# CPLD.net
KiCad netlist of a schematic drawn in Altium Designer
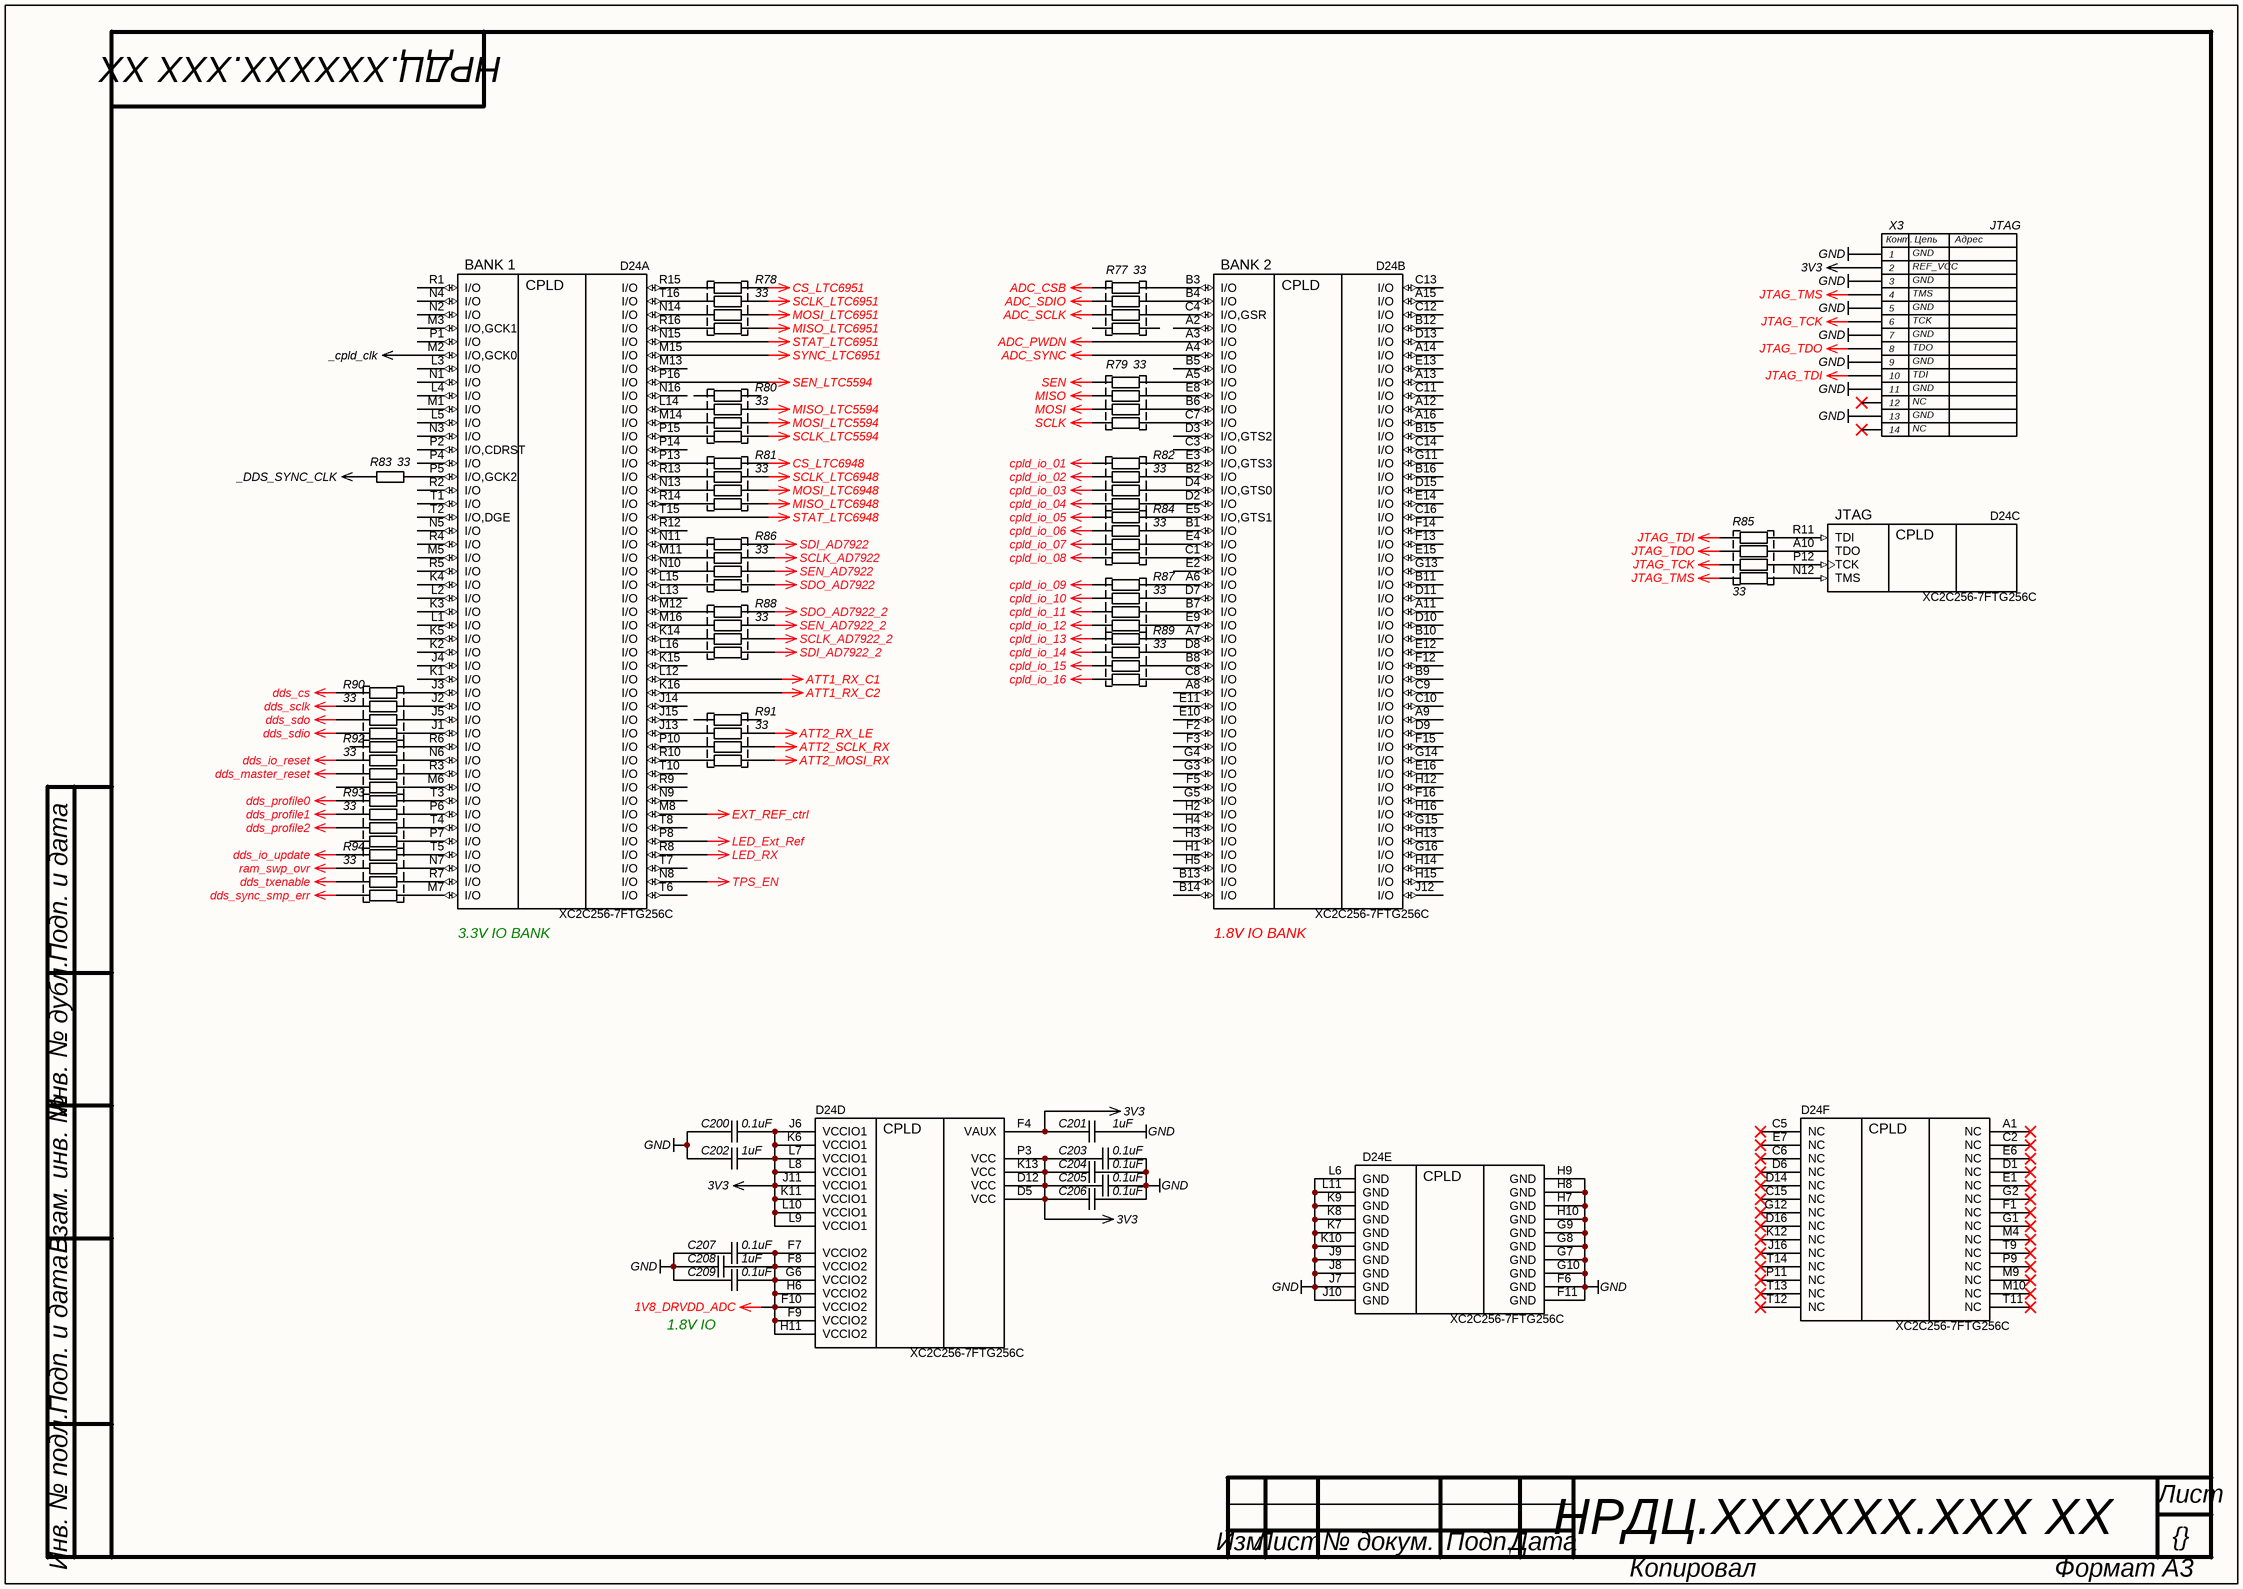
[diagram p0: CPLD.SchDoc]

(export (version "E")
  (design (tool "Eeschema 10.0.6"))
  (components
    (comp (ref "C200")
      (value "0.1uF")
      (footprint "C0402")
      (description "SMD Capacitor")
      (fields (field (name "MANUFACTURER") "Murata") (field (name "TOLERANCE") "10%"))
      (libsource (lib "Kintex_SDR") (part "CAP"))
    )
    (comp (ref "C201")
      (value "1uF")
      (footprint "C0402")
      (description "SMD Capacitor")
      (fields (field (name "MANUFACTURER") "Murata") (field (name "TOLERANCE") "10%"))
      (libsource (lib "Kintex_SDR") (part "CAP"))
    )
    (comp (ref "C202")
      (value "1uF")
      (footprint "C0402")
      (description "SMD Capacitor")
      (fields (field (name "MANUFACTURER") "Murata") (field (name "TOLERANCE") "10%"))
      (libsource (lib "Kintex_SDR") (part "CAP"))
    )
    (comp (ref "C203")
      (value "0.1uF")
      (footprint "C0402")
      (description "SMD Capacitor")
      (fields (field (name "MANUFACTURER") "Murata") (field (name "TOLERANCE") "10%"))
      (libsource (lib "Kintex_SDR") (part "CAP"))
    )
    (comp (ref "C204")
      (value "0.1uF")
      (footprint "C0402")
      (description "SMD Capacitor")
      (fields (field (name "MANUFACTURER") "Murata") (field (name "TOLERANCE") "10%"))
      (libsource (lib "Kintex_SDR") (part "CAP"))
    )
    (comp (ref "C205")
      (value "0.1uF")
      (footprint "C0402")
      (description "SMD Capacitor")
      (fields (field (name "MANUFACTURER") "Murata") (field (name "TOLERANCE") "10%"))
      (libsource (lib "Kintex_SDR") (part "CAP"))
    )
    (comp (ref "C206")
      (value "0.1uF")
      (footprint "C0402")
      (description "SMD Capacitor")
      (fields (field (name "MANUFACTURER") "Murata") (field (name "TOLERANCE") "10%"))
      (libsource (lib "Kintex_SDR") (part "CAP"))
    )
    (comp (ref "C207")
      (value "0.1uF")
      (footprint "C0402")
      (description "SMD Capacitor")
      (fields (field (name "MANUFACTURER") "Murata") (field (name "TOLERANCE") "10%"))
      (libsource (lib "Kintex_SDR") (part "CAP"))
    )
    (comp (ref "C208")
      (value "1uF")
      (footprint "C0402")
      (description "SMD Capacitor")
      (fields (field (name "MANUFACTURER") "Murata") (field (name "TOLERANCE") "10%"))
      (libsource (lib "Kintex_SDR") (part "CAP"))
    )
    (comp (ref "C209")
      (value "0.1uF")
      (footprint "C0402")
      (description "SMD Capacitor")
      (fields (field (name "MANUFACTURER") "Murata") (field (name "TOLERANCE") "10%"))
      (libsource (lib "Kintex_SDR") (part "CAP"))
    )
    (comp (ref "D24")
      (value "XC2C256-7FTG256C")
      (footprint "DBLib:FTG256")
      (description "CoolRunner-II 1.8V, 256 Macrocell CPLD, 184 User I/Os, 256-Ball FTBGA, Commercial Grade, Pb-Free")
      (libsource (lib "DBLib") (part "XC2C256-7FTG256C"))
    )
    (comp (ref "R77")
      (value "33")
      (footprint "EXN8V")
      (description "Chip Resistor Array")
      (fields (field (name "TOLERANCE") "5%") (field (name "MANUFACTURER") "Panasonic"))
      (libsource (lib "Kintex_SDR") (part "RES 4x0402"))
    )
    (comp (ref "R78")
      (value "33")
      (footprint "EXN8V")
      (description "Chip Resistor Array")
      (fields (field (name "TOLERANCE") "5%") (field (name "MANUFACTURER") "Panasonic"))
      (libsource (lib "Kintex_SDR") (part "RES 4x0402"))
    )
    (comp (ref "R79")
      (value "33")
      (footprint "EXN8V")
      (description "Chip Resistor Array")
      (fields (field (name "TOLERANCE") "5%") (field (name "MANUFACTURER") "Panasonic"))
      (libsource (lib "Kintex_SDR") (part "RES 4x0402"))
    )
    (comp (ref "R80")
      (value "33")
      (footprint "EXN8V")
      (description "Chip Resistor Array")
      (fields (field (name "TOLERANCE") "5%") (field (name "MANUFACTURER") "Panasonic"))
      (libsource (lib "Kintex_SDR") (part "RES 4x0402"))
    )
    (comp (ref "R81")
      (value "33")
      (footprint "EXN8V")
      (description "Chip Resistor Array")
      (fields (field (name "TOLERANCE") "5%") (field (name "MANUFACTURER") "Panasonic"))
      (libsource (lib "Kintex_SDR") (part "RES 4x0402"))
    )
    (comp (ref "R82")
      (value "33")
      (footprint "EXN8V")
      (description "Chip Resistor Array")
      (fields (field (name "TOLERANCE") "5%") (field (name "MANUFACTURER") "Panasonic"))
      (libsource (lib "Kintex_SDR") (part "RES 4x0402"))
    )
    (comp (ref "R83")
      (value "33")
      (footprint "R0402")
      (description "SMD Resistor")
      (fields (field (name "POWER") "0.062 Wt") (field (name "TOLERANCE") "5%"))
      (libsource (lib "Kintex_SDR") (part "RES"))
    )
    (comp (ref "R84")
      (value "33")
      (footprint "EXN8V")
      (description "Chip Resistor Array")
      (fields (field (name "TOLERANCE") "5%") (field (name "MANUFACTURER") "Panasonic"))
      (libsource (lib "Kintex_SDR") (part "RES 4x0402"))
    )
    (comp (ref "R85")
      (value "33")
      (footprint "EXN8V")
      (description "Chip Resistor Array")
      (fields (field (name "TOLERANCE") "5%") (field (name "MANUFACTURER") "Panasonic"))
      (libsource (lib "") (part "RES 4x0402_1"))
    )
    (comp (ref "R86")
      (value "33")
      (footprint "EXN8V")
      (description "Chip Resistor Array")
      (fields (field (name "TOLERANCE") "5%") (field (name "MANUFACTURER") "Panasonic"))
      (libsource (lib "Kintex_SDR") (part "RES 4x0402"))
    )
    (comp (ref "R87")
      (value "33")
      (footprint "EXN8V")
      (description "Chip Resistor Array")
      (fields (field (name "TOLERANCE") "5%") (field (name "MANUFACTURER") "Panasonic"))
      (libsource (lib "Kintex_SDR") (part "RES 4x0402"))
    )
    (comp (ref "R88")
      (value "33")
      (footprint "EXN8V")
      (description "Chip Resistor Array")
      (fields (field (name "TOLERANCE") "5%") (field (name "MANUFACTURER") "Panasonic"))
      (libsource (lib "Kintex_SDR") (part "RES 4x0402"))
    )
    (comp (ref "R89")
      (value "33")
      (footprint "EXN8V")
      (description "Chip Resistor Array")
      (fields (field (name "TOLERANCE") "5%") (field (name "MANUFACTURER") "Panasonic"))
      (libsource (lib "Kintex_SDR") (part "RES 4x0402"))
    )
    (comp (ref "R90")
      (value "33")
      (footprint "EXN8V")
      (description "Chip Resistor Array")
      (fields (field (name "TOLERANCE") "5%") (field (name "MANUFACTURER") "Panasonic"))
      (libsource (lib "Kintex_SDR") (part "RES 4x0402"))
    )
    (comp (ref "R91")
      (value "33")
      (footprint "EXN8V")
      (description "Chip Resistor Array")
      (fields (field (name "TOLERANCE") "5%") (field (name "MANUFACTURER") "Panasonic"))
      (libsource (lib "Kintex_SDR") (part "RES 4x0402"))
    )
    (comp (ref "R92")
      (value "33")
      (footprint "EXN8V")
      (description "Chip Resistor Array")
      (fields (field (name "TOLERANCE") "5%") (field (name "MANUFACTURER") "Panasonic"))
      (libsource (lib "Kintex_SDR") (part "RES 4x0402"))
    )
    (comp (ref "R93")
      (value "33")
      (footprint "EXN8V")
      (description "Chip Resistor Array")
      (fields (field (name "TOLERANCE") "5%") (field (name "MANUFACTURER") "Panasonic"))
      (libsource (lib "Kintex_SDR") (part "RES 4x0402"))
    )
    (comp (ref "R94")
      (value "33")
      (footprint "EXN8V")
      (description "Chip Resistor Array")
      (fields (field (name "TOLERANCE") "5%") (field (name "MANUFACTURER") "Panasonic"))
      (libsource (lib "Kintex_SDR") (part "RES 4x0402"))
    )
    (comp (ref "X3")
      (value "JTAG")
      (footprint "DBLib:JTAG Mail 2mm")
      (description "2.00mm Pitch, Milli-Grid PCB Header, Dual Row, Vertical, Through Hole, Shrouded, 14\r\nCircuits")
      (fields (field (name "MANUFACTURER") "Molex"))
      (libsource (lib "DBLib") (part "HDR Debug_14-pin"))
    )
  )
  (nets
    (net (code "1") (name "1V8_DRVDD_ADC") (class "Default")
      (node (ref "C207") (pin "2") (pinfunction "2_2") (pintype "passive"))
      (node (ref "C208") (pin "2") (pinfunction "2_2") (pintype "passive"))
      (node (ref "C209") (pin "2") (pinfunction "2_2") (pintype "passive"))
      (node (ref "D24") (pin "F10") (pinfunction "VCCIO2_F10") (pintype "power_in"))
      (node (ref "D24") (pin "F7") (pinfunction "VCCIO2_F7") (pintype "power_in"))
      (node (ref "D24") (pin "F8") (pinfunction "VCCIO2_F8") (pintype "power_in"))
      (node (ref "D24") (pin "F9") (pinfunction "VCCIO2_F9") (pintype "power_in"))
      (node (ref "D24") (pin "G6") (pinfunction "VCCIO2_G6") (pintype "power_in"))
      (node (ref "D24") (pin "H11") (pinfunction "VCCIO2_H11") (pintype "power_in"))
      (node (ref "D24") (pin "H6") (pinfunction "VCCIO2_H6") (pintype "power_in"))
    )
    (net (code "2") (name "3V3") (class "Default")
      (node (ref "C200") (pin "2") (pinfunction "2_2") (pintype "passive"))
      (node (ref "C201") (pin "1") (pinfunction "1_1") (pintype "passive"))
      (node (ref "C202") (pin "2") (pinfunction "2_2") (pintype "passive"))
      (node (ref "C203") (pin "1") (pinfunction "1_1") (pintype "passive"))
      (node (ref "C204") (pin "1") (pinfunction "1_1") (pintype "passive"))
      (node (ref "C205") (pin "1") (pinfunction "1_1") (pintype "passive"))
      (node (ref "C206") (pin "1") (pinfunction "1_1") (pintype "passive"))
      (node (ref "D24") (pin "D12") (pinfunction "VCC_D12") (pintype "power_in"))
      (node (ref "D24") (pin "D5") (pinfunction "VCC_D5") (pintype "power_in"))
      (node (ref "D24") (pin "F4") (pinfunction "VAUX_F4") (pintype "power_in"))
      (node (ref "D24") (pin "J11") (pinfunction "VCCIO1_J11") (pintype "power_in"))
      (node (ref "D24") (pin "J6") (pinfunction "VCCIO1_J6") (pintype "power_in"))
      (node (ref "D24") (pin "K11") (pinfunction "VCCIO1_K11") (pintype "power_in"))
      (node (ref "D24") (pin "K13") (pinfunction "VCC_K13") (pintype "power_in"))
      (node (ref "D24") (pin "K6") (pinfunction "VCCIO1_K6") (pintype "power_in"))
      (node (ref "D24") (pin "L10") (pinfunction "VCCIO1_L10") (pintype "power_in"))
      (node (ref "D24") (pin "L7") (pinfunction "VCCIO1_L7") (pintype "power_in"))
      (node (ref "D24") (pin "L8") (pinfunction "VCCIO1_L8") (pintype "power_in"))
      (node (ref "D24") (pin "L9") (pinfunction "VCCIO1_L9") (pintype "power_in"))
      (node (ref "D24") (pin "P3") (pinfunction "VCC_P3") (pintype "power_in"))
      (node (ref "X3") (pin "2") (pinfunction "2_2") (pintype "passive"))
    )
    (net (code "3") (name "ADC_CSB") (class "Default")
      (node (ref "R77") (pin "5") (pinfunction "5_5") (pintype "passive"))
    )
    (net (code "4") (name "ADC_PWDN") (class "Default")
      (node (ref "D24") (pin "A3") (pinfunction "I/O_A3") (pintype "bidirectional"))
    )
    (net (code "5") (name "ADC_SCLK") (class "Default")
      (node (ref "R77") (pin "7") (pinfunction "7_7") (pintype "passive"))
    )
    (net (code "6") (name "ADC_SDIO") (class "Default")
      (node (ref "R77") (pin "6") (pinfunction "6_6") (pintype "passive"))
    )
    (net (code "7") (name "ADC_SYNC") (class "Default")
      (node (ref "D24") (pin "A4") (pinfunction "I/O_A4") (pintype "bidirectional"))
    )
    (net (code "8") (name "ATT1_RX_C1") (class "Default")
      (node (ref "D24") (pin "L12") (pinfunction "I/O_L12") (pintype "bidirectional"))
    )
    (net (code "9") (name "ATT1_RX_C2") (class "Default")
      (node (ref "D24") (pin "K16") (pinfunction "I/O_K16") (pintype "bidirectional"))
    )
    (net (code "10") (name "ATT2_MOSI_RX") (class "Default")
      (node (ref "R91") (pin "1") (pinfunction "1_1") (pintype "passive"))
    )
    (net (code "11") (name "ATT2_RX_LE") (class "Default")
      (node (ref "R91") (pin "3") (pinfunction "3_3") (pintype "passive"))
    )
    (net (code "12") (name "ATT2_SCLK_RX") (class "Default")
      (node (ref "R91") (pin "2") (pinfunction "2_2") (pintype "passive"))
    )
    (net (code "13") (name "CS_LTC6948") (class "Default")
      (node (ref "R81") (pin "4") (pinfunction "4_4") (pintype "passive"))
    )
    (net (code "14") (name "CS_LTC6951") (class "Default")
      (node (ref "R78") (pin "4") (pinfunction "4_4") (pintype "passive"))
    )
    (net (code "15") (name "EXT_REF_ctrl") (class "Default")
      (node (ref "D24") (pin "M8") (pinfunction "I/O_M8") (pintype "bidirectional"))
    )
    (net (code "16") (name "GND") (class "Default")
      (node (ref "C200") (pin "1") (pinfunction "1_1") (pintype "passive"))
      (node (ref "C201") (pin "2") (pinfunction "2_2") (pintype "passive"))
      (node (ref "C202") (pin "1") (pinfunction "1_1") (pintype "passive"))
      (node (ref "C203") (pin "2") (pinfunction "2_2") (pintype "passive"))
      (node (ref "C204") (pin "2") (pinfunction "2_2") (pintype "passive"))
      (node (ref "C205") (pin "2") (pinfunction "2_2") (pintype "passive"))
      (node (ref "C206") (pin "2") (pinfunction "2_2") (pintype "passive"))
      (node (ref "C207") (pin "1") (pinfunction "1_1") (pintype "passive"))
      (node (ref "C208") (pin "1") (pinfunction "1_1") (pintype "passive"))
      (node (ref "C209") (pin "1") (pinfunction "1_1") (pintype "passive"))
      (node (ref "D24") (pin "F11") (pinfunction "GND_F11") (pintype "power_in"))
      (node (ref "D24") (pin "F6") (pinfunction "GND_F6") (pintype "power_in"))
      (node (ref "D24") (pin "G10") (pinfunction "GND_G10") (pintype "power_in"))
      (node (ref "D24") (pin "G7") (pinfunction "GND_G7") (pintype "power_in"))
      (node (ref "D24") (pin "G8") (pinfunction "GND_G8") (pintype "power_in"))
      (node (ref "D24") (pin "G9") (pinfunction "GND_G9") (pintype "power_in"))
      (node (ref "D24") (pin "H10") (pinfunction "GND_H10") (pintype "power_in"))
      (node (ref "D24") (pin "H7") (pinfunction "GND_H7") (pintype "power_in"))
      (node (ref "D24") (pin "H8") (pinfunction "GND_H8") (pintype "power_in"))
      (node (ref "D24") (pin "H9") (pinfunction "GND_H9") (pintype "power_in"))
      (node (ref "D24") (pin "J10") (pinfunction "GND_J10") (pintype "power_in"))
      (node (ref "D24") (pin "J7") (pinfunction "GND_J7") (pintype "power_in"))
      (node (ref "D24") (pin "J8") (pinfunction "GND_J8") (pintype "power_in"))
      (node (ref "D24") (pin "J9") (pinfunction "GND_J9") (pintype "power_in"))
      (node (ref "D24") (pin "K10") (pinfunction "GND_K10") (pintype "power_in"))
      (node (ref "D24") (pin "K7") (pinfunction "GND_K7") (pintype "power_in"))
      (node (ref "D24") (pin "K8") (pinfunction "GND_K8") (pintype "power_in"))
      (node (ref "D24") (pin "K9") (pinfunction "GND_K9") (pintype "power_in"))
      (node (ref "D24") (pin "L11") (pinfunction "GND_L11") (pintype "power_in"))
      (node (ref "D24") (pin "L6") (pinfunction "GND_L6") (pintype "power_in"))
      (node (ref "X3") (pin "1") (pinfunction "1_1") (pintype "passive"))
      (node (ref "X3") (pin "11") (pinfunction "11_11") (pintype "passive"))
      (node (ref "X3") (pin "13") (pinfunction "13_13") (pintype "passive"))
      (node (ref "X3") (pin "3") (pinfunction "3_3") (pintype "passive"))
      (node (ref "X3") (pin "5") (pinfunction "5_5") (pintype "passive"))
      (node (ref "X3") (pin "7") (pinfunction "7_7") (pintype "passive"))
      (node (ref "X3") (pin "9") (pinfunction "9_9") (pintype "passive"))
    )
    (net (code "17") (name "JTAG_TCK") (class "Default")
      (node (ref "R85") (pin "6") (pinfunction "6_6") (pintype "passive"))
      (node (ref "X3") (pin "6") (pinfunction "6_6") (pintype "passive"))
    )
    (net (code "18") (name "JTAG_TDI") (class "Default")
      (node (ref "R85") (pin "8") (pinfunction "8_8") (pintype "passive"))
      (node (ref "X3") (pin "10") (pinfunction "10_10") (pintype "passive"))
    )
    (net (code "19") (name "JTAG_TDO") (class "Default")
      (node (ref "R85") (pin "7") (pinfunction "7_7") (pintype "passive"))
      (node (ref "X3") (pin "8") (pinfunction "8_8") (pintype "passive"))
    )
    (net (code "20") (name "JTAG_TMS") (class "Default")
      (node (ref "R85") (pin "5") (pinfunction "5_5") (pintype "passive"))
      (node (ref "X3") (pin "4") (pinfunction "4_4") (pintype "passive"))
    )
    (net (code "21") (name "LED_Ext_Ref") (class "Default")
      (node (ref "D24") (pin "P8") (pinfunction "I/O_P8") (pintype "bidirectional"))
    )
    (net (code "22") (name "LED_RX") (class "Default")
      (node (ref "D24") (pin "R8") (pinfunction "I/O_R8") (pintype "bidirectional"))
    )
    (net (code "23") (name "MISO") (class "Default")
      (node (ref "R79") (pin "6") (pinfunction "6_6") (pintype "passive"))
    )
    (net (code "24") (name "MISO_LTC5594") (class "Default")
      (node (ref "R80") (pin "3") (pinfunction "3_3") (pintype "passive"))
    )
    (net (code "25") (name "MISO_LTC6948") (class "Default")
      (node (ref "R81") (pin "1") (pinfunction "1_1") (pintype "passive"))
    )
    (net (code "26") (name "MISO_LTC6951") (class "Default")
      (node (ref "R78") (pin "1") (pinfunction "1_1") (pintype "passive"))
    )
    (net (code "27") (name "MOSI") (class "Default")
      (node (ref "R79") (pin "7") (pinfunction "7_7") (pintype "passive"))
    )
    (net (code "28") (name "MOSI_LTC5594") (class "Default")
      (node (ref "R80") (pin "2") (pinfunction "2_2") (pintype "passive"))
    )
    (net (code "29") (name "MOSI_LTC6948") (class "Default")
      (node (ref "R81") (pin "2") (pinfunction "2_2") (pintype "passive"))
    )
    (net (code "30") (name "MOSI_LTC6951") (class "Default")
      (node (ref "R78") (pin "2") (pinfunction "2_2") (pintype "passive"))
    )
    (net (code "31") (name "Net-(D24A-I{slash}O,GCK2)") (class "Default")
      (node (ref "D24") (pin "P5") (pinfunction "I/O,GCK2_P5") (pintype "bidirectional"))
      (node (ref "R83") (pin "2") (pinfunction "2_2") (pintype "passive"))
    )
    (net (code "32") (name "Net-(D24A-I{slash}O-PadJ1)") (class "Default")
      (node (ref "D24") (pin "J1") (pinfunction "I/O_J1") (pintype "bidirectional"))
      (node (ref "R90") (pin "1") (pinfunction "1_1") (pintype "passive"))
    )
    (net (code "33") (name "Net-(D24A-I{slash}O-PadJ2)") (class "Default")
      (node (ref "D24") (pin "J2") (pinfunction "I/O_J2") (pintype "bidirectional"))
      (node (ref "R90") (pin "3") (pinfunction "3_3") (pintype "passive"))
    )
    (net (code "34") (name "Net-(D24A-I{slash}O-PadJ3)") (class "Default")
      (node (ref "D24") (pin "J3") (pinfunction "I/O_J3") (pintype "bidirectional"))
      (node (ref "R90") (pin "4") (pinfunction "4_4") (pintype "passive"))
    )
    (net (code "35") (name "Net-(D24A-I{slash}O-PadJ5)") (class "Default")
      (node (ref "D24") (pin "J5") (pinfunction "I/O_J5") (pintype "bidirectional"))
      (node (ref "R90") (pin "2") (pinfunction "2_2") (pintype "passive"))
    )
    (net (code "36") (name "Net-(D24A-I{slash}O-PadJ13)") (class "Default")
      (node (ref "D24") (pin "J13") (pinfunction "I/O_J13") (pintype "bidirectional"))
      (node (ref "R91") (pin "6") (pinfunction "6_6") (pintype "passive"))
    )
    (net (code "37") (name "Net-(D24A-I{slash}O-PadK14)") (class "Default")
      (node (ref "D24") (pin "K14") (pinfunction "I/O_K14") (pintype "bidirectional"))
      (node (ref "R88") (pin "7") (pinfunction "7_7") (pintype "passive"))
    )
    (net (code "38") (name "Net-(D24A-I{slash}O-PadL14)") (class "Default")
      (node (ref "D24") (pin "L14") (pinfunction "I/O_L14") (pintype "bidirectional"))
      (node (ref "R80") (pin "6") (pinfunction "6_6") (pintype "passive"))
    )
    (net (code "39") (name "Net-(D24A-I{slash}O-PadL15)") (class "Default")
      (node (ref "D24") (pin "L15") (pinfunction "I/O_L15") (pintype "bidirectional"))
      (node (ref "R86") (pin "8") (pinfunction "8_8") (pintype "passive"))
    )
    (net (code "40") (name "Net-(D24A-I{slash}O-PadL16)") (class "Default")
      (node (ref "D24") (pin "L16") (pinfunction "I/O_L16") (pintype "bidirectional"))
      (node (ref "R88") (pin "8") (pinfunction "8_8") (pintype "passive"))
    )
    (net (code "41") (name "Net-(D24A-I{slash}O-PadM6)") (class "Default")
      (node (ref "D24") (pin "M6") (pinfunction "I/O_M6") (pintype "bidirectional"))
      (node (ref "R92") (pin "1") (pinfunction "1_1") (pintype "passive"))
    )
    (net (code "42") (name "Net-(D24A-I{slash}O-PadM7)") (class "Default")
      (node (ref "D24") (pin "M7") (pinfunction "I/O_M7") (pintype "bidirectional"))
      (node (ref "R94") (pin "1") (pinfunction "1_1") (pintype "passive"))
    )
    (net (code "43") (name "Net-(D24A-I{slash}O-PadM11)") (class "Default")
      (node (ref "D24") (pin "M11") (pinfunction "I/O_M11") (pintype "bidirectional"))
      (node (ref "R86") (pin "6") (pinfunction "6_6") (pintype "passive"))
    )
    (net (code "44") (name "Net-(D24A-I{slash}O-PadM12)") (class "Default")
      (node (ref "D24") (pin "M12") (pinfunction "I/O_M12") (pintype "bidirectional"))
      (node (ref "R88") (pin "5") (pinfunction "5_5") (pintype "passive"))
    )
    (net (code "45") (name "Net-(D24A-I{slash}O-PadM14)") (class "Default")
      (node (ref "D24") (pin "M14") (pinfunction "I/O_M14") (pintype "bidirectional"))
      (node (ref "R80") (pin "7") (pinfunction "7_7") (pintype "passive"))
    )
    (net (code "46") (name "Net-(D24A-I{slash}O-PadM16)") (class "Default")
      (node (ref "D24") (pin "M16") (pinfunction "I/O_M16") (pintype "bidirectional"))
      (node (ref "R88") (pin "6") (pinfunction "6_6") (pintype "passive"))
    )
    (net (code "47") (name "Net-(D24A-I{slash}O-PadN6)") (class "Default")
      (node (ref "D24") (pin "N6") (pinfunction "I/O_N6") (pintype "bidirectional"))
      (node (ref "R92") (pin "3") (pinfunction "3_3") (pintype "passive"))
    )
    (net (code "48") (name "Net-(D24A-I{slash}O-PadN7)") (class "Default")
      (node (ref "D24") (pin "N7") (pinfunction "I/O_N7") (pintype "bidirectional"))
      (node (ref "R94") (pin "3") (pinfunction "3_3") (pintype "passive"))
    )
    (net (code "49") (name "Net-(D24A-I{slash}O-PadN10)") (class "Default")
      (node (ref "D24") (pin "N10") (pinfunction "I/O_N10") (pintype "bidirectional"))
      (node (ref "R86") (pin "7") (pinfunction "7_7") (pintype "passive"))
    )
    (net (code "50") (name "Net-(D24A-I{slash}O-PadN11)") (class "Default")
      (node (ref "D24") (pin "N11") (pinfunction "I/O_N11") (pintype "bidirectional"))
      (node (ref "R86") (pin "5") (pinfunction "5_5") (pintype "passive"))
    )
    (net (code "51") (name "Net-(D24A-I{slash}O-PadN13)") (class "Default")
      (node (ref "D24") (pin "N13") (pinfunction "I/O_N13") (pintype "bidirectional"))
      (node (ref "R81") (pin "7") (pinfunction "7_7") (pintype "passive"))
    )
    (net (code "52") (name "Net-(D24A-I{slash}O-PadN14)") (class "Default")
      (node (ref "D24") (pin "N14") (pinfunction "I/O_N14") (pintype "bidirectional"))
      (node (ref "R78") (pin "7") (pinfunction "7_7") (pintype "passive"))
    )
    (net (code "53") (name "Net-(D24A-I{slash}O-PadP6)") (class "Default")
      (node (ref "D24") (pin "P6") (pinfunction "I/O_P6") (pintype "bidirectional"))
      (node (ref "R93") (pin "3") (pinfunction "3_3") (pintype "passive"))
    )
    (net (code "54") (name "Net-(D24A-I{slash}O-PadP7)") (class "Default")
      (node (ref "D24") (pin "P7") (pinfunction "I/O_P7") (pintype "bidirectional"))
      (node (ref "R93") (pin "1") (pinfunction "1_1") (pintype "passive"))
    )
    (net (code "55") (name "Net-(D24A-I{slash}O-PadP10)") (class "Default")
      (node (ref "D24") (pin "P10") (pinfunction "I/O_P10") (pintype "bidirectional"))
      (node (ref "R91") (pin "7") (pinfunction "7_7") (pintype "passive"))
    )
    (net (code "56") (name "Net-(D24A-I{slash}O-PadP13)") (class "Default")
      (node (ref "D24") (pin "P13") (pinfunction "I/O_P13") (pintype "bidirectional"))
      (node (ref "R81") (pin "5") (pinfunction "5_5") (pintype "passive"))
    )
    (net (code "57") (name "Net-(D24A-I{slash}O-PadP15)") (class "Default")
      (node (ref "D24") (pin "P15") (pinfunction "I/O_P15") (pintype "bidirectional"))
      (node (ref "R80") (pin "8") (pinfunction "8_8") (pintype "passive"))
    )
    (net (code "58") (name "Net-(D24A-I{slash}O-PadR3)") (class "Default")
      (node (ref "D24") (pin "R3") (pinfunction "I/O_R3") (pintype "bidirectional"))
      (node (ref "R92") (pin "2") (pinfunction "2_2") (pintype "passive"))
    )
    (net (code "59") (name "Net-(D24A-I{slash}O-PadR6)") (class "Default")
      (node (ref "D24") (pin "R6") (pinfunction "I/O_R6") (pintype "bidirectional"))
      (node (ref "R92") (pin "4") (pinfunction "4_4") (pintype "passive"))
    )
    (net (code "60") (name "Net-(D24A-I{slash}O-PadR7)") (class "Default")
      (node (ref "D24") (pin "R7") (pinfunction "I/O_R7") (pintype "bidirectional"))
      (node (ref "R94") (pin "2") (pinfunction "2_2") (pintype "passive"))
    )
    (net (code "61") (name "Net-(D24A-I{slash}O-PadR10)") (class "Default")
      (node (ref "D24") (pin "R10") (pinfunction "I/O_R10") (pintype "bidirectional"))
      (node (ref "R91") (pin "8") (pinfunction "8_8") (pintype "passive"))
    )
    (net (code "62") (name "Net-(D24A-I{slash}O-PadR13)") (class "Default")
      (node (ref "D24") (pin "R13") (pinfunction "I/O_R13") (pintype "bidirectional"))
      (node (ref "R81") (pin "6") (pinfunction "6_6") (pintype "passive"))
    )
    (net (code "63") (name "Net-(D24A-I{slash}O-PadR14)") (class "Default")
      (node (ref "D24") (pin "R14") (pinfunction "I/O_R14") (pintype "bidirectional"))
      (node (ref "R81") (pin "8") (pinfunction "8_8") (pintype "passive"))
    )
    (net (code "64") (name "Net-(D24A-I{slash}O-PadR15)") (class "Default")
      (node (ref "D24") (pin "R15") (pinfunction "I/O_R15") (pintype "bidirectional"))
      (node (ref "R78") (pin "5") (pinfunction "5_5") (pintype "passive"))
    )
    (net (code "65") (name "Net-(D24A-I{slash}O-PadR16)") (class "Default")
      (node (ref "D24") (pin "R16") (pinfunction "I/O_R16") (pintype "bidirectional"))
      (node (ref "R78") (pin "8") (pinfunction "8_8") (pintype "passive"))
    )
    (net (code "66") (name "Net-(D24A-I{slash}O-PadT3)") (class "Default")
      (node (ref "D24") (pin "T3") (pinfunction "I/O_T3") (pintype "bidirectional"))
      (node (ref "R93") (pin "4") (pinfunction "4_4") (pintype "passive"))
    )
    (net (code "67") (name "Net-(D24A-I{slash}O-PadT4)") (class "Default")
      (node (ref "D24") (pin "T4") (pinfunction "I/O_T4") (pintype "bidirectional"))
      (node (ref "R93") (pin "2") (pinfunction "2_2") (pintype "passive"))
    )
    (net (code "68") (name "Net-(D24A-I{slash}O-PadT5)") (class "Default")
      (node (ref "D24") (pin "T5") (pinfunction "I/O_T5") (pintype "bidirectional"))
      (node (ref "R94") (pin "4") (pinfunction "4_4") (pintype "passive"))
    )
    (net (code "69") (name "Net-(D24A-I{slash}O-PadT16)") (class "Default")
      (node (ref "D24") (pin "T16") (pinfunction "I/O_T16") (pintype "bidirectional"))
      (node (ref "R78") (pin "6") (pinfunction "6_6") (pintype "passive"))
    )
    (net (code "70") (name "Net-(D24B-I{slash}O,GSR)") (class "Default")
      (node (ref "D24") (pin "C4") (pinfunction "I/O,GSR_C4") (pintype "bidirectional"))
      (node (ref "R77") (pin "2") (pinfunction "2_2") (pintype "passive"))
    )
    (net (code "71") (name "Net-(D24B-I{slash}O,GTS0)") (class "Default")
      (node (ref "D24") (pin "D4") (pinfunction "I/O,GTS0_D4") (pintype "bidirectional"))
      (node (ref "R82") (pin "2") (pinfunction "2_2") (pintype "passive"))
    )
    (net (code "72") (name "Net-(D24B-I{slash}O,GTS1)") (class "Default")
      (node (ref "D24") (pin "E5") (pinfunction "I/O,GTS1_E5") (pintype "bidirectional"))
      (node (ref "R84") (pin "4") (pinfunction "4_4") (pintype "passive"))
    )
    (net (code "73") (name "Net-(D24B-I{slash}O,GTS3)") (class "Default")
      (node (ref "D24") (pin "E3") (pinfunction "I/O,GTS3_E3") (pintype "bidirectional"))
      (node (ref "R82") (pin "4") (pinfunction "4_4") (pintype "passive"))
    )
    (net (code "74") (name "Net-(D24B-I{slash}O-PadA5)") (class "Default")
      (node (ref "D24") (pin "A5") (pinfunction "I/O_A5") (pintype "bidirectional"))
      (node (ref "R79") (pin "4") (pinfunction "4_4") (pintype "passive"))
    )
    (net (code "75") (name "Net-(D24B-I{slash}O-PadA6)") (class "Default")
      (node (ref "D24") (pin "A6") (pinfunction "I/O_A6") (pintype "bidirectional"))
      (node (ref "R87") (pin "4") (pinfunction "4_4") (pintype "passive"))
    )
    (net (code "76") (name "Net-(D24B-I{slash}O-PadA7)") (class "Default")
      (node (ref "D24") (pin "A7") (pinfunction "I/O_A7") (pintype "bidirectional"))
      (node (ref "R89") (pin "4") (pinfunction "4_4") (pintype "passive"))
    )
    (net (code "77") (name "Net-(D24B-I{slash}O-PadB1)") (class "Default")
      (node (ref "D24") (pin "B1") (pinfunction "I/O_B1") (pintype "bidirectional"))
      (node (ref "R84") (pin "3") (pinfunction "3_3") (pintype "passive"))
    )
    (net (code "78") (name "Net-(D24B-I{slash}O-PadB2)") (class "Default")
      (node (ref "D24") (pin "B2") (pinfunction "I/O_B2") (pintype "bidirectional"))
      (node (ref "R82") (pin "3") (pinfunction "3_3") (pintype "passive"))
    )
    (net (code "79") (name "Net-(D24B-I{slash}O-PadB3)") (class "Default")
      (node (ref "D24") (pin "B3") (pinfunction "I/O_B3") (pintype "bidirectional"))
      (node (ref "R77") (pin "4") (pinfunction "4_4") (pintype "passive"))
    )
    (net (code "80") (name "Net-(D24B-I{slash}O-PadB4)") (class "Default")
      (node (ref "D24") (pin "B4") (pinfunction "I/O_B4") (pintype "bidirectional"))
      (node (ref "R77") (pin "3") (pinfunction "3_3") (pintype "passive"))
    )
    (net (code "81") (name "Net-(D24B-I{slash}O-PadB6)") (class "Default")
      (node (ref "D24") (pin "B6") (pinfunction "I/O_B6") (pintype "bidirectional"))
      (node (ref "R79") (pin "2") (pinfunction "2_2") (pintype "passive"))
    )
    (net (code "82") (name "Net-(D24B-I{slash}O-PadB7)") (class "Default")
      (node (ref "D24") (pin "B7") (pinfunction "I/O_B7") (pintype "bidirectional"))
      (node (ref "R87") (pin "2") (pinfunction "2_2") (pintype "passive"))
    )
    (net (code "83") (name "Net-(D24B-I{slash}O-PadB8)") (class "Default")
      (node (ref "D24") (pin "B8") (pinfunction "I/O_B8") (pintype "bidirectional"))
      (node (ref "R89") (pin "2") (pinfunction "2_2") (pintype "passive"))
    )
    (net (code "84") (name "Net-(D24B-I{slash}O-PadC1)") (class "Default")
      (node (ref "D24") (pin "C1") (pinfunction "I/O_C1") (pintype "bidirectional"))
      (node (ref "R84") (pin "1") (pinfunction "1_1") (pintype "passive"))
    )
    (net (code "85") (name "Net-(D24B-I{slash}O-PadC7)") (class "Default")
      (node (ref "D24") (pin "C7") (pinfunction "I/O_C7") (pintype "bidirectional"))
      (node (ref "R79") (pin "1") (pinfunction "1_1") (pintype "passive"))
    )
    (net (code "86") (name "Net-(D24B-I{slash}O-PadC8)") (class "Default")
      (node (ref "D24") (pin "C8") (pinfunction "I/O_C8") (pintype "bidirectional"))
      (node (ref "R89") (pin "1") (pinfunction "1_1") (pintype "passive"))
    )
    (net (code "87") (name "Net-(D24B-I{slash}O-PadD2)") (class "Default")
      (node (ref "D24") (pin "D2") (pinfunction "I/O_D2") (pintype "bidirectional"))
      (node (ref "R82") (pin "1") (pinfunction "1_1") (pintype "passive"))
    )
    (net (code "88") (name "Net-(D24B-I{slash}O-PadD7)") (class "Default")
      (node (ref "D24") (pin "D7") (pinfunction "I/O_D7") (pintype "bidirectional"))
      (node (ref "R87") (pin "3") (pinfunction "3_3") (pintype "passive"))
    )
    (net (code "89") (name "Net-(D24B-I{slash}O-PadD8)") (class "Default")
      (node (ref "D24") (pin "D8") (pinfunction "I/O_D8") (pintype "bidirectional"))
      (node (ref "R89") (pin "3") (pinfunction "3_3") (pintype "passive"))
    )
    (net (code "90") (name "Net-(D24B-I{slash}O-PadE4)") (class "Default")
      (node (ref "D24") (pin "E4") (pinfunction "I/O_E4") (pintype "bidirectional"))
      (node (ref "R84") (pin "2") (pinfunction "2_2") (pintype "passive"))
    )
    (net (code "91") (name "Net-(D24B-I{slash}O-PadE8)") (class "Default")
      (node (ref "D24") (pin "E8") (pinfunction "I/O_E8") (pintype "bidirectional"))
      (node (ref "R79") (pin "3") (pinfunction "3_3") (pintype "passive"))
    )
    (net (code "92") (name "Net-(D24B-I{slash}O-PadE9)") (class "Default")
      (node (ref "D24") (pin "E9") (pinfunction "I/O_E9") (pintype "bidirectional"))
      (node (ref "R87") (pin "1") (pinfunction "1_1") (pintype "passive"))
    )
    (net (code "93") (name "Net-(D24C-TCK)") (class "Default")
      (node (ref "D24") (pin "P12") (pinfunction "TCK_P12") (pintype "input"))
      (node (ref "R85") (pin "3") (pinfunction "3_3") (pintype "passive"))
    )
    (net (code "94") (name "Net-(D24C-TDI)") (class "Default")
      (node (ref "D24") (pin "R11") (pinfunction "TDI_R11") (pintype "input"))
      (node (ref "R85") (pin "1") (pinfunction "1_1") (pintype "passive"))
    )
    (net (code "95") (name "Net-(D24C-TDO)") (class "Default")
      (node (ref "D24") (pin "A10") (pinfunction "TDO_A10") (pintype "passive"))
      (node (ref "R85") (pin "2") (pinfunction "2_2") (pintype "passive"))
    )
    (net (code "96") (name "Net-(D24C-TMS)") (class "Default")
      (node (ref "D24") (pin "N12") (pinfunction "TMS_N12") (pintype "input"))
      (node (ref "R85") (pin "4") (pinfunction "4_4") (pintype "passive"))
    )
    (net (code "97") (name "SCLK") (class "Default")
      (node (ref "R79") (pin "8") (pinfunction "8_8") (pintype "passive"))
    )
    (net (code "98") (name "SCLK_AD7922") (class "Default")
      (node (ref "R86") (pin "3") (pinfunction "3_3") (pintype "passive"))
    )
    (net (code "99") (name "SCLK_AD7922_2") (class "Default")
      (node (ref "R88") (pin "2") (pinfunction "2_2") (pintype "passive"))
    )
    (net (code "100") (name "SCLK_LTC5594") (class "Default")
      (node (ref "R80") (pin "1") (pinfunction "1_1") (pintype "passive"))
    )
    (net (code "101") (name "SCLK_LTC6948") (class "Default")
      (node (ref "R81") (pin "3") (pinfunction "3_3") (pintype "passive"))
    )
    (net (code "102") (name "SCLK_LTC6951") (class "Default")
      (node (ref "R78") (pin "3") (pinfunction "3_3") (pintype "passive"))
    )
    (net (code "103") (name "SDI_AD7922") (class "Default")
      (node (ref "R86") (pin "4") (pinfunction "4_4") (pintype "passive"))
    )
    (net (code "104") (name "SDI_AD7922_2") (class "Default")
      (node (ref "R88") (pin "1") (pinfunction "1_1") (pintype "passive"))
    )
    (net (code "105") (name "SDO_AD7922") (class "Default")
      (node (ref "R86") (pin "1") (pinfunction "1_1") (pintype "passive"))
    )
    (net (code "106") (name "SDO_AD7922_2") (class "Default")
      (node (ref "R88") (pin "4") (pinfunction "4_4") (pintype "passive"))
    )
    (net (code "107") (name "SEN") (class "Default")
      (node (ref "R79") (pin "5") (pinfunction "5_5") (pintype "passive"))
    )
    (net (code "108") (name "SEN_AD7922") (class "Default")
      (node (ref "R86") (pin "2") (pinfunction "2_2") (pintype "passive"))
    )
    (net (code "109") (name "SEN_AD7922_2") (class "Default")
      (node (ref "R88") (pin "3") (pinfunction "3_3") (pintype "passive"))
    )
    (net (code "110") (name "SEN_LTC5594") (class "Default")
      (node (ref "D24") (pin "P16") (pinfunction "I/O_P16") (pintype "bidirectional"))
    )
    (net (code "111") (name "STAT_LTC6948") (class "Default")
      (node (ref "D24") (pin "T15") (pinfunction "I/O_T15") (pintype "bidirectional"))
    )
    (net (code "112") (name "STAT_LTC6951") (class "Default")
      (node (ref "D24") (pin "N15") (pinfunction "I/O_N15") (pintype "bidirectional"))
    )
    (net (code "113") (name "SYNC_LTC6951") (class "Default")
      (node (ref "D24") (pin "M15") (pinfunction "I/O_M15") (pintype "bidirectional"))
    )
    (net (code "114") (name "TPS_EN") (class "Default")
      (node (ref "D24") (pin "N8") (pinfunction "I/O_N8") (pintype "bidirectional"))
    )
    (net (code "115") (name "_DDS_SYNC_CLK") (class "Default")
      (node (ref "R83") (pin "1") (pinfunction "1_1") (pintype "passive"))
    )
    (net (code "116") (name "_cpld_clk") (class "Default")
      (node (ref "D24") (pin "M2") (pinfunction "I/O,GCK0_M2") (pintype "bidirectional"))
    )
    (net (code "117") (name "cpld_io_01") (class "Default")
      (node (ref "R82") (pin "5") (pinfunction "5_5") (pintype "passive"))
    )
    (net (code "118") (name "cpld_io_02") (class "Default")
      (node (ref "R82") (pin "6") (pinfunction "6_6") (pintype "passive"))
    )
    (net (code "119") (name "cpld_io_03") (class "Default")
      (node (ref "R82") (pin "7") (pinfunction "7_7") (pintype "passive"))
    )
    (net (code "120") (name "cpld_io_04") (class "Default")
      (node (ref "R82") (pin "8") (pinfunction "8_8") (pintype "passive"))
    )
    (net (code "121") (name "cpld_io_05") (class "Default")
      (node (ref "R84") (pin "5") (pinfunction "5_5") (pintype "passive"))
    )
    (net (code "122") (name "cpld_io_06") (class "Default")
      (node (ref "R84") (pin "6") (pinfunction "6_6") (pintype "passive"))
    )
    (net (code "123") (name "cpld_io_07") (class "Default")
      (node (ref "R84") (pin "7") (pinfunction "7_7") (pintype "passive"))
    )
    (net (code "124") (name "cpld_io_08") (class "Default")
      (node (ref "R84") (pin "8") (pinfunction "8_8") (pintype "passive"))
    )
    (net (code "125") (name "cpld_io_09") (class "Default")
      (node (ref "R87") (pin "5") (pinfunction "5_5") (pintype "passive"))
    )
    (net (code "126") (name "cpld_io_10") (class "Default")
      (node (ref "R87") (pin "6") (pinfunction "6_6") (pintype "passive"))
    )
    (net (code "127") (name "cpld_io_11") (class "Default")
      (node (ref "R87") (pin "7") (pinfunction "7_7") (pintype "passive"))
    )
    (net (code "128") (name "cpld_io_12") (class "Default")
      (node (ref "R87") (pin "8") (pinfunction "8_8") (pintype "passive"))
    )
    (net (code "129") (name "cpld_io_13") (class "Default")
      (node (ref "R89") (pin "5") (pinfunction "5_5") (pintype "passive"))
    )
    (net (code "130") (name "cpld_io_14") (class "Default")
      (node (ref "R89") (pin "6") (pinfunction "6_6") (pintype "passive"))
    )
    (net (code "131") (name "cpld_io_15") (class "Default")
      (node (ref "R89") (pin "7") (pinfunction "7_7") (pintype "passive"))
    )
    (net (code "132") (name "cpld_io_16") (class "Default")
      (node (ref "R89") (pin "8") (pinfunction "8_8") (pintype "passive"))
    )
    (net (code "133") (name "dds_cs") (class "Default")
      (node (ref "R90") (pin "5") (pinfunction "5_5") (pintype "passive"))
    )
    (net (code "134") (name "dds_io_reset") (class "Default")
      (node (ref "R92") (pin "6") (pinfunction "6_6") (pintype "passive"))
    )
    (net (code "135") (name "dds_io_update") (class "Default")
      (node (ref "R94") (pin "5") (pinfunction "5_5") (pintype "passive"))
    )
    (net (code "136") (name "dds_master_reset") (class "Default")
      (node (ref "R92") (pin "7") (pinfunction "7_7") (pintype "passive"))
    )
    (net (code "137") (name "dds_profile0") (class "Default")
      (node (ref "R93") (pin "5") (pinfunction "5_5") (pintype "passive"))
    )
    (net (code "138") (name "dds_profile1") (class "Default")
      (node (ref "R93") (pin "6") (pinfunction "6_6") (pintype "passive"))
    )
    (net (code "139") (name "dds_profile2") (class "Default")
      (node (ref "R93") (pin "7") (pinfunction "7_7") (pintype "passive"))
    )
    (net (code "140") (name "dds_sclk") (class "Default")
      (node (ref "R90") (pin "6") (pinfunction "6_6") (pintype "passive"))
    )
    (net (code "141") (name "dds_sdio") (class "Default")
      (node (ref "R90") (pin "8") (pinfunction "8_8") (pintype "passive"))
    )
    (net (code "142") (name "dds_sdo") (class "Default")
      (node (ref "R90") (pin "7") (pinfunction "7_7") (pintype "passive"))
    )
    (net (code "143") (name "dds_sync_smp_err") (class "Default")
      (node (ref "R94") (pin "8") (pinfunction "8_8") (pintype "passive"))
    )
    (net (code "144") (name "dds_txenable") (class "Default")
      (node (ref "R94") (pin "7") (pinfunction "7_7") (pintype "passive"))
    )
    (net (code "145") (name "ram_swp_ovr") (class "Default")
      (node (ref "R94") (pin "6") (pinfunction "6_6") (pintype "passive"))
    )
    (net (code "146") (name "unconnected-(D24A-I{slash}O,CDRST-PadP2)") (class "Default")
      (node (ref "D24") (pin "P2") (pinfunction "I/O,CDRST_P2") (pintype "bidirectional"))
    )
    (net (code "147") (name "unconnected-(D24A-I{slash}O,DGE-PadT2)") (class "Default")
      (node (ref "D24") (pin "T2") (pinfunction "I/O,DGE_T2") (pintype "bidirectional"))
    )
    (net (code "148") (name "unconnected-(D24A-I{slash}O,GCK1-PadM3)") (class "Default")
      (node (ref "D24") (pin "M3") (pinfunction "I/O,GCK1_M3") (pintype "bidirectional"))
    )
    (net (code "149") (name "unconnected-(D24A-I{slash}O-PadJ4)") (class "Default")
      (node (ref "D24") (pin "J4") (pinfunction "I/O_J4") (pintype "bidirectional"))
    )
    (net (code "150") (name "unconnected-(D24A-I{slash}O-PadJ14)") (class "Default")
      (node (ref "D24") (pin "J14") (pinfunction "I/O_J14") (pintype "bidirectional"))
    )
    (net (code "151") (name "unconnected-(D24A-I{slash}O-PadJ15)") (class "Default")
      (node (ref "D24") (pin "J15") (pinfunction "I/O_J15") (pintype "bidirectional"))
    )
    (net (code "152") (name "unconnected-(D24A-I{slash}O-PadK1)") (class "Default")
      (node (ref "D24") (pin "K1") (pinfunction "I/O_K1") (pintype "bidirectional"))
    )
    (net (code "153") (name "unconnected-(D24A-I{slash}O-PadK2)") (class "Default")
      (node (ref "D24") (pin "K2") (pinfunction "I/O_K2") (pintype "bidirectional"))
    )
    (net (code "154") (name "unconnected-(D24A-I{slash}O-PadK3)") (class "Default")
      (node (ref "D24") (pin "K3") (pinfunction "I/O_K3") (pintype "bidirectional"))
    )
    (net (code "155") (name "unconnected-(D24A-I{slash}O-PadK4)") (class "Default")
      (node (ref "D24") (pin "K4") (pinfunction "I/O_K4") (pintype "bidirectional"))
    )
    (net (code "156") (name "unconnected-(D24A-I{slash}O-PadK5)") (class "Default")
      (node (ref "D24") (pin "K5") (pinfunction "I/O_K5") (pintype "bidirectional"))
    )
    (net (code "157") (name "unconnected-(D24A-I{slash}O-PadK15)") (class "Default")
      (node (ref "D24") (pin "K15") (pinfunction "I/O_K15") (pintype "bidirectional"))
    )
    (net (code "158") (name "unconnected-(D24A-I{slash}O-PadL1)") (class "Default")
      (node (ref "D24") (pin "L1") (pinfunction "I/O_L1") (pintype "bidirectional"))
    )
    (net (code "159") (name "unconnected-(D24A-I{slash}O-PadL2)") (class "Default")
      (node (ref "D24") (pin "L2") (pinfunction "I/O_L2") (pintype "bidirectional"))
    )
    (net (code "160") (name "unconnected-(D24A-I{slash}O-PadL3)") (class "Default")
      (node (ref "D24") (pin "L3") (pinfunction "I/O_L3") (pintype "bidirectional"))
    )
    (net (code "161") (name "unconnected-(D24A-I{slash}O-PadL4)") (class "Default")
      (node (ref "D24") (pin "L4") (pinfunction "I/O_L4") (pintype "bidirectional"))
    )
    (net (code "162") (name "unconnected-(D24A-I{slash}O-PadL5)") (class "Default")
      (node (ref "D24") (pin "L5") (pinfunction "I/O_L5") (pintype "bidirectional"))
    )
    (net (code "163") (name "unconnected-(D24A-I{slash}O-PadL13)") (class "Default")
      (node (ref "D24") (pin "L13") (pinfunction "I/O_L13") (pintype "bidirectional"))
    )
    (net (code "164") (name "unconnected-(D24A-I{slash}O-PadM1)") (class "Default")
      (node (ref "D24") (pin "M1") (pinfunction "I/O_M1") (pintype "bidirectional"))
    )
    (net (code "165") (name "unconnected-(D24A-I{slash}O-PadM5)") (class "Default")
      (node (ref "D24") (pin "M5") (pinfunction "I/O_M5") (pintype "bidirectional"))
    )
    (net (code "166") (name "unconnected-(D24A-I{slash}O-PadM13)") (class "Default")
      (node (ref "D24") (pin "M13") (pinfunction "I/O_M13") (pintype "bidirectional"))
    )
    (net (code "167") (name "unconnected-(D24A-I{slash}O-PadN1)") (class "Default")
      (node (ref "D24") (pin "N1") (pinfunction "I/O_N1") (pintype "bidirectional"))
    )
    (net (code "168") (name "unconnected-(D24A-I{slash}O-PadN2)") (class "Default")
      (node (ref "D24") (pin "N2") (pinfunction "I/O_N2") (pintype "bidirectional"))
    )
    (net (code "169") (name "unconnected-(D24A-I{slash}O-PadN3)") (class "Default")
      (node (ref "D24") (pin "N3") (pinfunction "I/O_N3") (pintype "bidirectional"))
    )
    (net (code "170") (name "unconnected-(D24A-I{slash}O-PadN4)") (class "Default")
      (node (ref "D24") (pin "N4") (pinfunction "I/O_N4") (pintype "bidirectional"))
    )
    (net (code "171") (name "unconnected-(D24A-I{slash}O-PadN5)") (class "Default")
      (node (ref "D24") (pin "N5") (pinfunction "I/O_N5") (pintype "bidirectional"))
    )
    (net (code "172") (name "unconnected-(D24A-I{slash}O-PadN9)") (class "Default")
      (node (ref "D24") (pin "N9") (pinfunction "I/O_N9") (pintype "bidirectional"))
    )
    (net (code "173") (name "unconnected-(D24A-I{slash}O-PadN16)") (class "Default")
      (node (ref "D24") (pin "N16") (pinfunction "I/O_N16") (pintype "bidirectional"))
    )
    (net (code "174") (name "unconnected-(D24A-I{slash}O-PadP1)") (class "Default")
      (node (ref "D24") (pin "P1") (pinfunction "I/O_P1") (pintype "bidirectional"))
    )
    (net (code "175") (name "unconnected-(D24A-I{slash}O-PadP4)") (class "Default")
      (node (ref "D24") (pin "P4") (pinfunction "I/O_P4") (pintype "bidirectional"))
    )
    (net (code "176") (name "unconnected-(D24A-I{slash}O-PadP14)") (class "Default")
      (node (ref "D24") (pin "P14") (pinfunction "I/O_P14") (pintype "bidirectional"))
    )
    (net (code "177") (name "unconnected-(D24A-I{slash}O-PadR1)") (class "Default")
      (node (ref "D24") (pin "R1") (pinfunction "I/O_R1") (pintype "bidirectional"))
    )
    (net (code "178") (name "unconnected-(D24A-I{slash}O-PadR2)") (class "Default")
      (node (ref "D24") (pin "R2") (pinfunction "I/O_R2") (pintype "bidirectional"))
    )
    (net (code "179") (name "unconnected-(D24A-I{slash}O-PadR4)") (class "Default")
      (node (ref "D24") (pin "R4") (pinfunction "I/O_R4") (pintype "bidirectional"))
    )
    (net (code "180") (name "unconnected-(D24A-I{slash}O-PadR5)") (class "Default")
      (node (ref "D24") (pin "R5") (pinfunction "I/O_R5") (pintype "bidirectional"))
    )
    (net (code "181") (name "unconnected-(D24A-I{slash}O-PadR9)") (class "Default")
      (node (ref "D24") (pin "R9") (pinfunction "I/O_R9") (pintype "bidirectional"))
    )
    (net (code "182") (name "unconnected-(D24A-I{slash}O-PadR12)") (class "Default")
      (node (ref "D24") (pin "R12") (pinfunction "I/O_R12") (pintype "bidirectional"))
    )
    (net (code "183") (name "unconnected-(D24A-I{slash}O-PadT1)") (class "Default")
      (node (ref "D24") (pin "T1") (pinfunction "I/O_T1") (pintype "bidirectional"))
    )
    (net (code "184") (name "unconnected-(D24A-I{slash}O-PadT6)") (class "Default")
      (node (ref "D24") (pin "T6") (pinfunction "I/O_T6") (pintype "bidirectional"))
    )
    (net (code "185") (name "unconnected-(D24A-I{slash}O-PadT7)") (class "Default")
      (node (ref "D24") (pin "T7") (pinfunction "I/O_T7") (pintype "bidirectional"))
    )
    (net (code "186") (name "unconnected-(D24A-I{slash}O-PadT8)") (class "Default")
      (node (ref "D24") (pin "T8") (pinfunction "I/O_T8") (pintype "bidirectional"))
    )
    (net (code "187") (name "unconnected-(D24A-I{slash}O-PadT10)") (class "Default")
      (node (ref "D24") (pin "T10") (pinfunction "I/O_T10") (pintype "bidirectional"))
    )
    (net (code "188") (name "unconnected-(D24B-I{slash}O,GTS2-PadD3)") (class "Default")
      (node (ref "D24") (pin "D3") (pinfunction "I/O,GTS2_D3") (pintype "bidirectional"))
    )
    (net (code "189") (name "unconnected-(D24B-I{slash}O-PadA2)") (class "Default")
      (node (ref "D24") (pin "A2") (pinfunction "I/O_A2") (pintype "bidirectional"))
    )
    (net (code "190") (name "unconnected-(D24B-I{slash}O-PadA8)") (class "Default")
      (node (ref "D24") (pin "A8") (pinfunction "I/O_A8") (pintype "bidirectional"))
    )
    (net (code "191") (name "unconnected-(D24B-I{slash}O-PadA9)") (class "Default")
      (node (ref "D24") (pin "A9") (pinfunction "I/O_A9") (pintype "bidirectional"))
    )
    (net (code "192") (name "unconnected-(D24B-I{slash}O-PadA11)") (class "Default")
      (node (ref "D24") (pin "A11") (pinfunction "I/O_A11") (pintype "bidirectional"))
    )
    (net (code "193") (name "unconnected-(D24B-I{slash}O-PadA12)") (class "Default")
      (node (ref "D24") (pin "A12") (pinfunction "I/O_A12") (pintype "bidirectional"))
    )
    (net (code "194") (name "unconnected-(D24B-I{slash}O-PadA13)") (class "Default")
      (node (ref "D24") (pin "A13") (pinfunction "I/O_A13") (pintype "bidirectional"))
    )
    (net (code "195") (name "unconnected-(D24B-I{slash}O-PadA14)") (class "Default")
      (node (ref "D24") (pin "A14") (pinfunction "I/O_A14") (pintype "bidirectional"))
    )
    (net (code "196") (name "unconnected-(D24B-I{slash}O-PadA15)") (class "Default")
      (node (ref "D24") (pin "A15") (pinfunction "I/O_A15") (pintype "bidirectional"))
    )
    (net (code "197") (name "unconnected-(D24B-I{slash}O-PadA16)") (class "Default")
      (node (ref "D24") (pin "A16") (pinfunction "I/O_A16") (pintype "bidirectional"))
    )
    (net (code "198") (name "unconnected-(D24B-I{slash}O-PadB5)") (class "Default")
      (node (ref "D24") (pin "B5") (pinfunction "I/O_B5") (pintype "bidirectional"))
    )
    (net (code "199") (name "unconnected-(D24B-I{slash}O-PadB9)") (class "Default")
      (node (ref "D24") (pin "B9") (pinfunction "I/O_B9") (pintype "bidirectional"))
    )
    (net (code "200") (name "unconnected-(D24B-I{slash}O-PadB10)") (class "Default")
      (node (ref "D24") (pin "B10") (pinfunction "I/O_B10") (pintype "bidirectional"))
    )
    (net (code "201") (name "unconnected-(D24B-I{slash}O-PadB11)") (class "Default")
      (node (ref "D24") (pin "B11") (pinfunction "I/O_B11") (pintype "bidirectional"))
    )
    (net (code "202") (name "unconnected-(D24B-I{slash}O-PadB12)") (class "Default")
      (node (ref "D24") (pin "B12") (pinfunction "I/O_B12") (pintype "bidirectional"))
    )
    (net (code "203") (name "unconnected-(D24B-I{slash}O-PadB13)") (class "Default")
      (node (ref "D24") (pin "B13") (pinfunction "I/O_B13") (pintype "bidirectional"))
    )
    (net (code "204") (name "unconnected-(D24B-I{slash}O-PadB14)") (class "Default")
      (node (ref "D24") (pin "B14") (pinfunction "I/O_B14") (pintype "bidirectional"))
    )
    (net (code "205") (name "unconnected-(D24B-I{slash}O-PadB15)") (class "Default")
      (node (ref "D24") (pin "B15") (pinfunction "I/O_B15") (pintype "bidirectional"))
    )
    (net (code "206") (name "unconnected-(D24B-I{slash}O-PadB16)") (class "Default")
      (node (ref "D24") (pin "B16") (pinfunction "I/O_B16") (pintype "bidirectional"))
    )
    (net (code "207") (name "unconnected-(D24B-I{slash}O-PadC3)") (class "Default")
      (node (ref "D24") (pin "C3") (pinfunction "I/O_C3") (pintype "bidirectional"))
    )
    (net (code "208") (name "unconnected-(D24B-I{slash}O-PadC9)") (class "Default")
      (node (ref "D24") (pin "C9") (pinfunction "I/O_C9") (pintype "bidirectional"))
    )
    (net (code "209") (name "unconnected-(D24B-I{slash}O-PadC10)") (class "Default")
      (node (ref "D24") (pin "C10") (pinfunction "I/O_C10") (pintype "bidirectional"))
    )
    (net (code "210") (name "unconnected-(D24B-I{slash}O-PadC11)") (class "Default")
      (node (ref "D24") (pin "C11") (pinfunction "I/O_C11") (pintype "bidirectional"))
    )
    (net (code "211") (name "unconnected-(D24B-I{slash}O-PadC12)") (class "Default")
      (node (ref "D24") (pin "C12") (pinfunction "I/O_C12") (pintype "bidirectional"))
    )
    (net (code "212") (name "unconnected-(D24B-I{slash}O-PadC13)") (class "Default")
      (node (ref "D24") (pin "C13") (pinfunction "I/O_C13") (pintype "bidirectional"))
    )
    (net (code "213") (name "unconnected-(D24B-I{slash}O-PadC14)") (class "Default")
      (node (ref "D24") (pin "C14") (pinfunction "I/O_C14") (pintype "bidirectional"))
    )
    (net (code "214") (name "unconnected-(D24B-I{slash}O-PadC16)") (class "Default")
      (node (ref "D24") (pin "C16") (pinfunction "I/O_C16") (pintype "bidirectional"))
    )
    (net (code "215") (name "unconnected-(D24B-I{slash}O-PadD9)") (class "Default")
      (node (ref "D24") (pin "D9") (pinfunction "I/O_D9") (pintype "bidirectional"))
    )
    (net (code "216") (name "unconnected-(D24B-I{slash}O-PadD10)") (class "Default")
      (node (ref "D24") (pin "D10") (pinfunction "I/O_D10") (pintype "bidirectional"))
    )
    (net (code "217") (name "unconnected-(D24B-I{slash}O-PadD11)") (class "Default")
      (node (ref "D24") (pin "D11") (pinfunction "I/O_D11") (pintype "bidirectional"))
    )
    (net (code "218") (name "unconnected-(D24B-I{slash}O-PadD13)") (class "Default")
      (node (ref "D24") (pin "D13") (pinfunction "I/O_D13") (pintype "bidirectional"))
    )
    (net (code "219") (name "unconnected-(D24B-I{slash}O-PadD15)") (class "Default")
      (node (ref "D24") (pin "D15") (pinfunction "I/O_D15") (pintype "bidirectional"))
    )
    (net (code "220") (name "unconnected-(D24B-I{slash}O-PadE2)") (class "Default")
      (node (ref "D24") (pin "E2") (pinfunction "I/O_E2") (pintype "bidirectional"))
    )
    (net (code "221") (name "unconnected-(D24B-I{slash}O-PadE10)") (class "Default")
      (node (ref "D24") (pin "E10") (pinfunction "I/O_E10") (pintype "bidirectional"))
    )
    (net (code "222") (name "unconnected-(D24B-I{slash}O-PadE11)") (class "Default")
      (node (ref "D24") (pin "E11") (pinfunction "I/O_E11") (pintype "bidirectional"))
    )
    (net (code "223") (name "unconnected-(D24B-I{slash}O-PadE12)") (class "Default")
      (node (ref "D24") (pin "E12") (pinfunction "I/O_E12") (pintype "bidirectional"))
    )
    (net (code "224") (name "unconnected-(D24B-I{slash}O-PadE13)") (class "Default")
      (node (ref "D24") (pin "E13") (pinfunction "I/O_E13") (pintype "bidirectional"))
    )
    (net (code "225") (name "unconnected-(D24B-I{slash}O-PadE14)") (class "Default")
      (node (ref "D24") (pin "E14") (pinfunction "I/O_E14") (pintype "bidirectional"))
    )
    (net (code "226") (name "unconnected-(D24B-I{slash}O-PadE15)") (class "Default")
      (node (ref "D24") (pin "E15") (pinfunction "I/O_E15") (pintype "bidirectional"))
    )
    (net (code "227") (name "unconnected-(D24B-I{slash}O-PadE16)") (class "Default")
      (node (ref "D24") (pin "E16") (pinfunction "I/O_E16") (pintype "bidirectional"))
    )
    (net (code "228") (name "unconnected-(D24B-I{slash}O-PadF2)") (class "Default")
      (node (ref "D24") (pin "F2") (pinfunction "I/O_F2") (pintype "bidirectional"))
    )
    (net (code "229") (name "unconnected-(D24B-I{slash}O-PadF3)") (class "Default")
      (node (ref "D24") (pin "F3") (pinfunction "I/O_F3") (pintype "bidirectional"))
    )
    (net (code "230") (name "unconnected-(D24B-I{slash}O-PadF5)") (class "Default")
      (node (ref "D24") (pin "F5") (pinfunction "I/O_F5") (pintype "bidirectional"))
    )
    (net (code "231") (name "unconnected-(D24B-I{slash}O-PadF12)") (class "Default")
      (node (ref "D24") (pin "F12") (pinfunction "I/O_F12") (pintype "bidirectional"))
    )
    (net (code "232") (name "unconnected-(D24B-I{slash}O-PadF13)") (class "Default")
      (node (ref "D24") (pin "F13") (pinfunction "I/O_F13") (pintype "bidirectional"))
    )
    (net (code "233") (name "unconnected-(D24B-I{slash}O-PadF14)") (class "Default")
      (node (ref "D24") (pin "F14") (pinfunction "I/O_F14") (pintype "bidirectional"))
    )
    (net (code "234") (name "unconnected-(D24B-I{slash}O-PadF15)") (class "Default")
      (node (ref "D24") (pin "F15") (pinfunction "I/O_F15") (pintype "bidirectional"))
    )
    (net (code "235") (name "unconnected-(D24B-I{slash}O-PadF16)") (class "Default")
      (node (ref "D24") (pin "F16") (pinfunction "I/O_F16") (pintype "bidirectional"))
    )
    (net (code "236") (name "unconnected-(D24B-I{slash}O-PadG3)") (class "Default")
      (node (ref "D24") (pin "G3") (pinfunction "I/O_G3") (pintype "bidirectional"))
    )
    (net (code "237") (name "unconnected-(D24B-I{slash}O-PadG4)") (class "Default")
      (node (ref "D24") (pin "G4") (pinfunction "I/O_G4") (pintype "bidirectional"))
    )
    (net (code "238") (name "unconnected-(D24B-I{slash}O-PadG5)") (class "Default")
      (node (ref "D24") (pin "G5") (pinfunction "I/O_G5") (pintype "bidirectional"))
    )
    (net (code "239") (name "unconnected-(D24B-I{slash}O-PadG11)") (class "Default")
      (node (ref "D24") (pin "G11") (pinfunction "I/O_G11") (pintype "bidirectional"))
    )
    (net (code "240") (name "unconnected-(D24B-I{slash}O-PadG13)") (class "Default")
      (node (ref "D24") (pin "G13") (pinfunction "I/O_G13") (pintype "bidirectional"))
    )
    (net (code "241") (name "unconnected-(D24B-I{slash}O-PadG14)") (class "Default")
      (node (ref "D24") (pin "G14") (pinfunction "I/O_G14") (pintype "bidirectional"))
    )
    (net (code "242") (name "unconnected-(D24B-I{slash}O-PadG15)") (class "Default")
      (node (ref "D24") (pin "G15") (pinfunction "I/O_G15") (pintype "bidirectional"))
    )
    (net (code "243") (name "unconnected-(D24B-I{slash}O-PadG16)") (class "Default")
      (node (ref "D24") (pin "G16") (pinfunction "I/O_G16") (pintype "bidirectional"))
    )
    (net (code "244") (name "unconnected-(D24B-I{slash}O-PadH1)") (class "Default")
      (node (ref "D24") (pin "H1") (pinfunction "I/O_H1") (pintype "bidirectional"))
    )
    (net (code "245") (name "unconnected-(D24B-I{slash}O-PadH2)") (class "Default")
      (node (ref "D24") (pin "H2") (pinfunction "I/O_H2") (pintype "bidirectional"))
    )
    (net (code "246") (name "unconnected-(D24B-I{slash}O-PadH3)") (class "Default")
      (node (ref "D24") (pin "H3") (pinfunction "I/O_H3") (pintype "bidirectional"))
    )
    (net (code "247") (name "unconnected-(D24B-I{slash}O-PadH4)") (class "Default")
      (node (ref "D24") (pin "H4") (pinfunction "I/O_H4") (pintype "bidirectional"))
    )
    (net (code "248") (name "unconnected-(D24B-I{slash}O-PadH5)") (class "Default")
      (node (ref "D24") (pin "H5") (pinfunction "I/O_H5") (pintype "bidirectional"))
    )
    (net (code "249") (name "unconnected-(D24B-I{slash}O-PadH12)") (class "Default")
      (node (ref "D24") (pin "H12") (pinfunction "I/O_H12") (pintype "bidirectional"))
    )
    (net (code "250") (name "unconnected-(D24B-I{slash}O-PadH13)") (class "Default")
      (node (ref "D24") (pin "H13") (pinfunction "I/O_H13") (pintype "bidirectional"))
    )
    (net (code "251") (name "unconnected-(D24B-I{slash}O-PadH14)") (class "Default")
      (node (ref "D24") (pin "H14") (pinfunction "I/O_H14") (pintype "bidirectional"))
    )
    (net (code "252") (name "unconnected-(D24B-I{slash}O-PadH15)") (class "Default")
      (node (ref "D24") (pin "H15") (pinfunction "I/O_H15") (pintype "bidirectional"))
    )
    (net (code "253") (name "unconnected-(D24B-I{slash}O-PadH16)") (class "Default")
      (node (ref "D24") (pin "H16") (pinfunction "I/O_H16") (pintype "bidirectional"))
    )
    (net (code "254") (name "unconnected-(D24B-I{slash}O-PadJ12)") (class "Default")
      (node (ref "D24") (pin "J12") (pinfunction "I/O_J12") (pintype "bidirectional"))
    )
    (net (code "255") (name "unconnected-(D24F-NC-PadA1)") (class "Default")
      (node (ref "D24") (pin "A1") (pinfunction "NC_A1") (pintype "passive+no_connect"))
    )
    (net (code "256") (name "unconnected-(D24F-NC-PadC2)") (class "Default")
      (node (ref "D24") (pin "C2") (pinfunction "NC_C2") (pintype "passive+no_connect"))
    )
    (net (code "257") (name "unconnected-(D24F-NC-PadC5)") (class "Default")
      (node (ref "D24") (pin "C5") (pinfunction "NC_C5") (pintype "passive+no_connect"))
    )
    (net (code "258") (name "unconnected-(D24F-NC-PadC6)") (class "Default")
      (node (ref "D24") (pin "C6") (pinfunction "NC_C6") (pintype "passive+no_connect"))
    )
    (net (code "259") (name "unconnected-(D24F-NC-PadC15)") (class "Default")
      (node (ref "D24") (pin "C15") (pinfunction "NC_C15") (pintype "passive+no_connect"))
    )
    (net (code "260") (name "unconnected-(D24F-NC-PadD1)") (class "Default")
      (node (ref "D24") (pin "D1") (pinfunction "NC_D1") (pintype "passive+no_connect"))
    )
    (net (code "261") (name "unconnected-(D24F-NC-PadD6)") (class "Default")
      (node (ref "D24") (pin "D6") (pinfunction "NC_D6") (pintype "passive+no_connect"))
    )
    (net (code "262") (name "unconnected-(D24F-NC-PadD14)") (class "Default")
      (node (ref "D24") (pin "D14") (pinfunction "NC_D14") (pintype "passive+no_connect"))
    )
    (net (code "263") (name "unconnected-(D24F-NC-PadD16)") (class "Default")
      (node (ref "D24") (pin "D16") (pinfunction "NC_D16") (pintype "passive+no_connect"))
    )
    (net (code "264") (name "unconnected-(D24F-NC-PadE1)") (class "Default")
      (node (ref "D24") (pin "E1") (pinfunction "NC_E1") (pintype "passive+no_connect"))
    )
    (net (code "265") (name "unconnected-(D24F-NC-PadE6)") (class "Default")
      (node (ref "D24") (pin "E6") (pinfunction "NC_E6") (pintype "passive+no_connect"))
    )
    (net (code "266") (name "unconnected-(D24F-NC-PadE7)") (class "Default")
      (node (ref "D24") (pin "E7") (pinfunction "NC_E7") (pintype "passive+no_connect"))
    )
    (net (code "267") (name "unconnected-(D24F-NC-PadF1)") (class "Default")
      (node (ref "D24") (pin "F1") (pinfunction "NC_F1") (pintype "passive+no_connect"))
    )
    (net (code "268") (name "unconnected-(D24F-NC-PadG1)") (class "Default")
      (node (ref "D24") (pin "G1") (pinfunction "NC_G1") (pintype "passive+no_connect"))
    )
    (net (code "269") (name "unconnected-(D24F-NC-PadG2)") (class "Default")
      (node (ref "D24") (pin "G2") (pinfunction "NC_G2") (pintype "passive+no_connect"))
    )
    (net (code "270") (name "unconnected-(D24F-NC-PadG12)") (class "Default")
      (node (ref "D24") (pin "G12") (pinfunction "NC_G12") (pintype "passive+no_connect"))
    )
    (net (code "271") (name "unconnected-(D24F-NC-PadJ16)") (class "Default")
      (node (ref "D24") (pin "J16") (pinfunction "NC_J16") (pintype "passive+no_connect"))
    )
    (net (code "272") (name "unconnected-(D24F-NC-PadK12)") (class "Default")
      (node (ref "D24") (pin "K12") (pinfunction "NC_K12") (pintype "passive+no_connect"))
    )
    (net (code "273") (name "unconnected-(D24F-NC-PadM4)") (class "Default")
      (node (ref "D24") (pin "M4") (pinfunction "NC_M4") (pintype "passive+no_connect"))
    )
    (net (code "274") (name "unconnected-(D24F-NC-PadM9)") (class "Default")
      (node (ref "D24") (pin "M9") (pinfunction "NC_M9") (pintype "passive+no_connect"))
    )
    (net (code "275") (name "unconnected-(D24F-NC-PadM10)") (class "Default")
      (node (ref "D24") (pin "M10") (pinfunction "NC_M10") (pintype "passive+no_connect"))
    )
    (net (code "276") (name "unconnected-(D24F-NC-PadP9)") (class "Default")
      (node (ref "D24") (pin "P9") (pinfunction "NC_P9") (pintype "passive+no_connect"))
    )
    (net (code "277") (name "unconnected-(D24F-NC-PadP11)") (class "Default")
      (node (ref "D24") (pin "P11") (pinfunction "NC_P11") (pintype "passive+no_connect"))
    )
    (net (code "278") (name "unconnected-(D24F-NC-PadT9)") (class "Default")
      (node (ref "D24") (pin "T9") (pinfunction "NC_T9") (pintype "passive+no_connect"))
    )
    (net (code "279") (name "unconnected-(D24F-NC-PadT11)") (class "Default")
      (node (ref "D24") (pin "T11") (pinfunction "NC_T11") (pintype "passive+no_connect"))
    )
    (net (code "280") (name "unconnected-(D24F-NC-PadT12)") (class "Default")
      (node (ref "D24") (pin "T12") (pinfunction "NC_T12") (pintype "passive+no_connect"))
    )
    (net (code "281") (name "unconnected-(D24F-NC-PadT13)") (class "Default")
      (node (ref "D24") (pin "T13") (pinfunction "NC_T13") (pintype "passive+no_connect"))
    )
    (net (code "282") (name "unconnected-(D24F-NC-PadT14)") (class "Default")
      (node (ref "D24") (pin "T14") (pinfunction "NC_T14") (pintype "passive+no_connect"))
    )
    (net (code "283") (name "unconnected-(R77-Pad1)") (class "Default")
      (node (ref "R77") (pin "1") (pinfunction "1_1") (pintype "passive"))
    )
    (net (code "284") (name "unconnected-(R77-Pad8)") (class "Default")
      (node (ref "R77") (pin "8") (pinfunction "8_8") (pintype "passive"))
    )
    (net (code "285") (name "unconnected-(R80-Pad4)") (class "Default")
      (node (ref "R80") (pin "4") (pinfunction "4_4") (pintype "passive"))
    )
    (net (code "286") (name "unconnected-(R80-Pad5)") (class "Default")
      (node (ref "R80") (pin "5") (pinfunction "5_5") (pintype "passive"))
    )
    (net (code "287") (name "unconnected-(R91-Pad4)") (class "Default")
      (node (ref "R91") (pin "4") (pinfunction "4_4") (pintype "passive"))
    )
    (net (code "288") (name "unconnected-(R91-Pad5)") (class "Default")
      (node (ref "R91") (pin "5") (pinfunction "5_5") (pintype "passive"))
    )
    (net (code "289") (name "unconnected-(R92-Pad5)") (class "Default")
      (node (ref "R92") (pin "5") (pinfunction "5_5") (pintype "passive"))
    )
    (net (code "290") (name "unconnected-(R92-Pad8)") (class "Default")
      (node (ref "R92") (pin "8") (pinfunction "8_8") (pintype "passive"))
    )
    (net (code "291") (name "unconnected-(R93-Pad8)") (class "Default")
      (node (ref "R93") (pin "8") (pinfunction "8_8") (pintype "passive"))
    )
    (net (code "292") (name "unconnected-(X3-Pad12)") (class "Default")
      (node (ref "X3") (pin "12") (pinfunction "12_12") (pintype "passive+no_connect"))
    )
    (net (code "293") (name "unconnected-(X3-Pad14)") (class "Default")
      (node (ref "X3") (pin "14") (pinfunction "14_14") (pintype "passive+no_connect"))
    )
  )
)
